# Jednoruki_bandit.net
KiCad netlist of a schematic drawn in Altium Designer
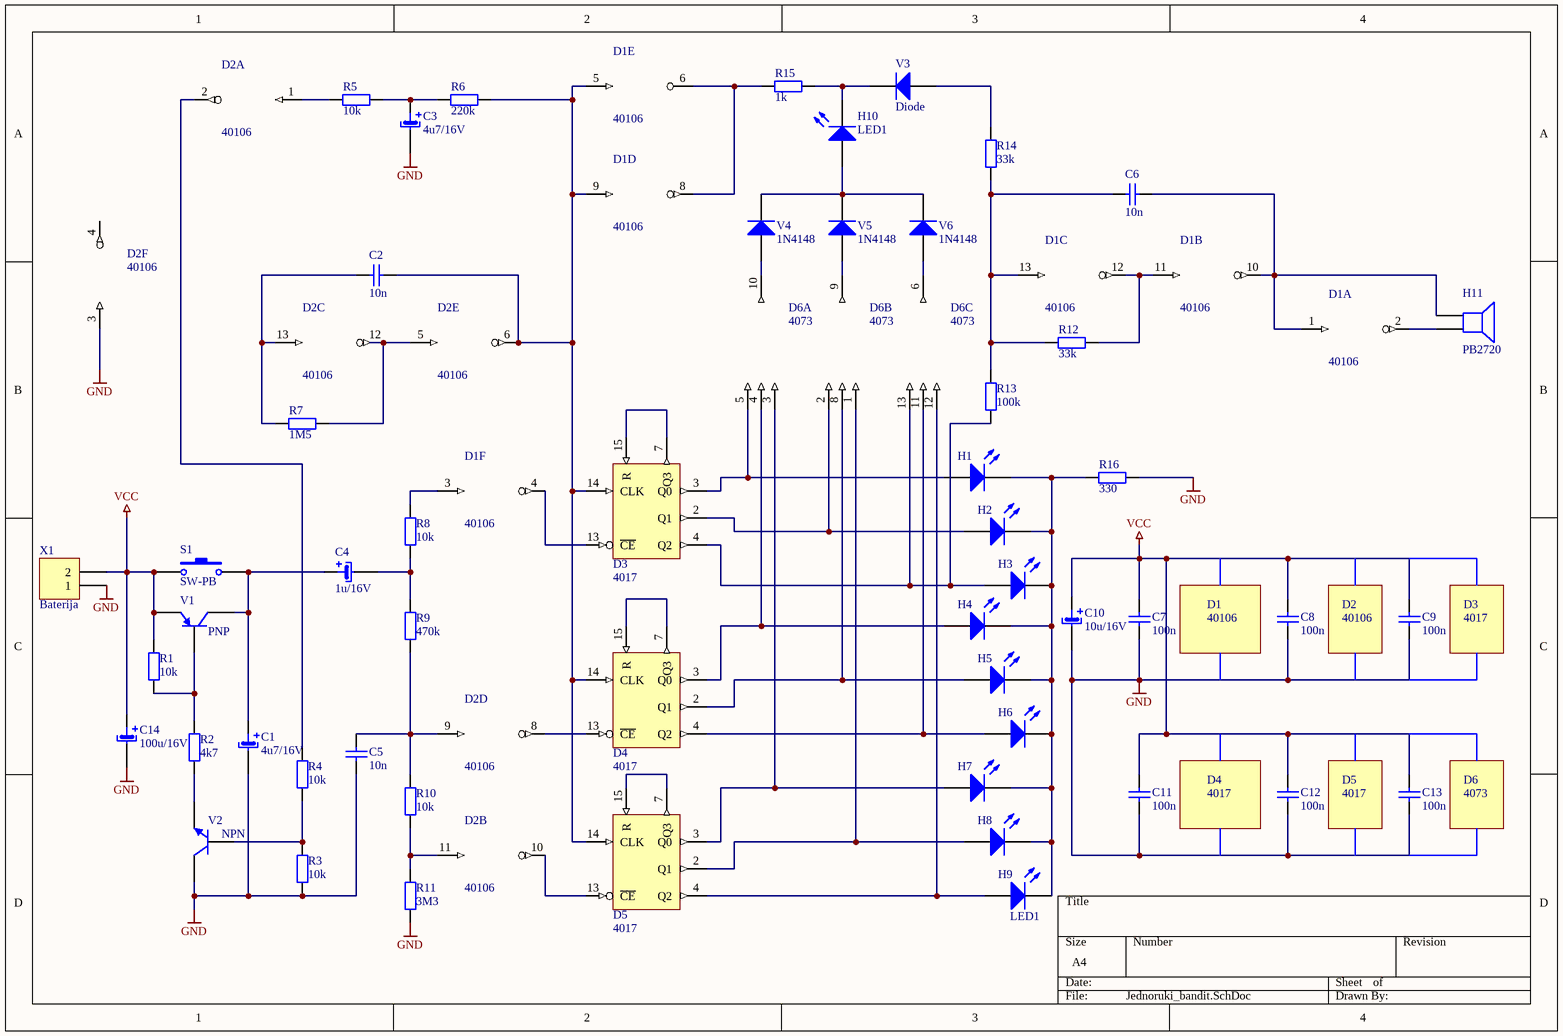
[diagram p0: Jednoruki_bandit.SchDoc]

(export (version "E")
  (design (tool "Eeschema 10.0.6"))
  (components
    (comp (ref "C1")
      (value "4u7/16V")
      (footprint "CAPPR2-5x6.8")
      (libsource (lib "moje") (part "Elektrolitski_kondenzator"))
    )
    (comp (ref "C2")
      (value "10n")
      (footprint "RAD-0.1")
      (description "Capacitor")
      (libsource (lib "Miscellaneous Devices") (part "Cap"))
    )
    (comp (ref "C3")
      (value "4u7/16V")
      (footprint "CAPPR2-5x6.8")
      (libsource (lib "moje") (part "Elektrolitski_kondenzator"))
    )
    (comp (ref "C4")
      (value "1u/16V")
      (footprint "CAPPR2-5x6.8")
      (libsource (lib "moje") (part "Elektrolitski_kondenzator"))
    )
    (comp (ref "C5")
      (value "10n")
      (footprint "RAD-0.1")
      (description "Capacitor")
      (libsource (lib "Miscellaneous Devices") (part "Cap"))
    )
    (comp (ref "C6")
      (value "10n")
      (footprint "RAD-0.1")
      (description "Capacitor")
      (libsource (lib "Miscellaneous Devices") (part "Cap"))
    )
    (comp (ref "C7")
      (value "100n")
      (footprint "RAD-0.1")
      (description "Capacitor")
      (libsource (lib "Miscellaneous Devices") (part "Cap"))
    )
    (comp (ref "C8")
      (value "100n")
      (footprint "RAD-0.1")
      (description "Capacitor")
      (libsource (lib "Miscellaneous Devices") (part "Cap"))
    )
    (comp (ref "C9")
      (value "100n")
      (footprint "RAD-0.1")
      (description "Capacitor")
      (libsource (lib "Miscellaneous Devices") (part "Cap"))
    )
    (comp (ref "C10")
      (value "10u/16V")
      (footprint "CAPPR2-5x6.8")
      (libsource (lib "moje") (part "Elektrolitski_kondenzator"))
    )
    (comp (ref "C11")
      (value "100n")
      (footprint "RAD-0.1")
      (description "Capacitor")
      (libsource (lib "Miscellaneous Devices") (part "Cap"))
    )
    (comp (ref "C12")
      (value "100n")
      (footprint "RAD-0.1")
      (description "Capacitor")
      (libsource (lib "Miscellaneous Devices") (part "Cap"))
    )
    (comp (ref "C13")
      (value "100n")
      (footprint "RAD-0.1")
      (description "Capacitor")
      (libsource (lib "Miscellaneous Devices") (part "Cap"))
    )
    (comp (ref "C14")
      (value "100u/16V")
      (footprint "CAPPR2-5x6.8")
      (libsource (lib "moje") (part "Elektrolitski_kondenzator"))
    )
    (comp (ref "D1") (value "40106") (footprint "DIP-14") (libsource (lib "moje") (part "40106")))
    (comp (ref "D2") (value "40106") (footprint "DIP-14") (libsource (lib "moje") (part "40106")))
    (comp (ref "D3") (value "4017") (footprint "DIP-16") (libsource (lib "moje") (part "4017")))
    (comp (ref "D4") (value "4017") (footprint "DIP-16") (libsource (lib "moje") (part "4017")))
    (comp (ref "D5") (value "4017") (footprint "DIP-16") (libsource (lib "moje") (part "4017")))
    (comp (ref "D6") (value "4073") (footprint "DIP-14") (libsource (lib "moje") (part "4073")))
    (comp (ref "H1")
      (value "LED1")
      (footprint "LED-1")
      (description "Typical RED GaAs LED")
      (libsource (lib "Miscellaneous Devices") (part "LED1"))
    )
    (comp (ref "H2")
      (value "LED1")
      (footprint "LED-1")
      (description "Typical RED GaAs LED")
      (libsource (lib "Miscellaneous Devices") (part "LED1"))
    )
    (comp (ref "H3")
      (value "LED1")
      (footprint "LED-1")
      (description "Typical RED GaAs LED")
      (libsource (lib "Miscellaneous Devices") (part "LED1"))
    )
    (comp (ref "H4")
      (value "LED1")
      (footprint "LED-1")
      (description "Typical RED GaAs LED")
      (libsource (lib "Miscellaneous Devices") (part "LED1"))
    )
    (comp (ref "H5")
      (value "LED1")
      (footprint "LED-1")
      (description "Typical RED GaAs LED")
      (libsource (lib "Miscellaneous Devices") (part "LED1"))
    )
    (comp (ref "H6")
      (value "LED1")
      (footprint "LED-1")
      (description "Typical RED GaAs LED")
      (libsource (lib "Miscellaneous Devices") (part "LED1"))
    )
    (comp (ref "H7")
      (value "LED1")
      (footprint "LED-1")
      (description "Typical RED GaAs LED")
      (libsource (lib "Miscellaneous Devices") (part "LED1"))
    )
    (comp (ref "H8")
      (value "LED1")
      (footprint "LED-1")
      (description "Typical RED GaAs LED")
      (libsource (lib "Miscellaneous Devices") (part "LED1"))
    )
    (comp (ref "H9")
      (value "LED1")
      (footprint "LED-1")
      (description "Typical RED GaAs LED")
      (libsource (lib "Miscellaneous Devices") (part "LED1"))
    )
    (comp (ref "H10")
      (value "LED1")
      (footprint "LED-1")
      (description "Typical RED GaAs LED")
      (libsource (lib "Miscellaneous Devices") (part "LED1"))
    )
    (comp (ref "H11")
      (value "PB2720")
      (footprint "PIN2")
      (description "Loudspeaker")
      (libsource (lib "Miscellaneous Devices") (part "Speaker"))
    )
    (comp (ref "R1")
      (value "10k")
      (footprint "AXIAL-0.4")
      (description "Resistor")
      (libsource (lib "") (part "Res2_1"))
    )
    (comp (ref "R2")
      (value "4k7")
      (footprint "AXIAL-0.4")
      (description "Resistor")
      (libsource (lib "") (part "Res2_1"))
    )
    (comp (ref "R3")
      (value "10k")
      (footprint "AXIAL-0.4")
      (description "Resistor")
      (libsource (lib "") (part "Res2_1"))
    )
    (comp (ref "R4")
      (value "10k")
      (footprint "AXIAL-0.4")
      (description "Resistor")
      (libsource (lib "") (part "Res2_1"))
    )
    (comp (ref "R5")
      (value "10k")
      (footprint "AXIAL-0.4")
      (description "Resistor")
      (libsource (lib "Miscellaneous Devices") (part "Res2"))
    )
    (comp (ref "R6")
      (value "220k")
      (footprint "AXIAL-0.4")
      (description "Resistor")
      (libsource (lib "Miscellaneous Devices") (part "Res2"))
    )
    (comp (ref "R7")
      (value "1M5")
      (footprint "AXIAL-0.4")
      (description "Resistor")
      (libsource (lib "Miscellaneous Devices") (part "Res2"))
    )
    (comp (ref "R8")
      (value "10k")
      (footprint "AXIAL-0.4")
      (description "Resistor")
      (libsource (lib "") (part "Res2_1"))
    )
    (comp (ref "R9")
      (value "470k")
      (footprint "AXIAL-0.4")
      (description "Resistor")
      (libsource (lib "") (part "Res2_1"))
    )
    (comp (ref "R10")
      (value "10k")
      (footprint "AXIAL-0.4")
      (description "Resistor")
      (libsource (lib "") (part "Res2_1"))
    )
    (comp (ref "R11")
      (value "3M3")
      (footprint "AXIAL-0.4")
      (description "Resistor")
      (libsource (lib "") (part "Res2_1"))
    )
    (comp (ref "R12")
      (value "33k")
      (footprint "AXIAL-0.4")
      (description "Resistor")
      (libsource (lib "") (part "Res2_2"))
    )
    (comp (ref "R13")
      (value "100k")
      (footprint "AXIAL-0.4")
      (description "Resistor")
      (libsource (lib "") (part "Res2_1"))
    )
    (comp (ref "R14")
      (value "33k")
      (footprint "AXIAL-0.4")
      (description "Resistor")
      (libsource (lib "") (part "Res2_1"))
    )
    (comp (ref "R15")
      (value "1k")
      (footprint "AXIAL-0.4")
      (description "Resistor")
      (libsource (lib "Miscellaneous Devices") (part "Res2"))
    )
    (comp (ref "R16")
      (value "330")
      (footprint "AXIAL-0.4")
      (description "Resistor")
      (libsource (lib "Miscellaneous Devices") (part "Res2"))
    )
    (comp (ref "S1")
      (value "SW-PB")
      (footprint "SPST-2")
      (description "Switch")
      (libsource (lib "Miscellaneous Devices") (part "SW-PB"))
    )
    (comp (ref "V1")
      (value "PNP")
      (footprint "TO-92A")
      (description "PNP Bipolar Transistor")
      (libsource (lib "Miscellaneous Devices") (part "PNP"))
    )
    (comp (ref "V2")
      (value "NPN")
      (footprint "TO-92A")
      (description "NPN Bipolar Transistor")
      (libsource (lib "Miscellaneous Devices") (part "NPN"))
    )
    (comp (ref "V3")
      (value "Diode")
      (footprint "DO-35")
      (description "Default Diode")
      (libsource (lib "Miscellaneous Devices") (part "Diode"))
    )
    (comp (ref "V4")
      (value "1N4148")
      (footprint "DIO7.1-3.9x1.9")
      (description "High Conductance Fast Diode")
      (libsource (lib "Miscellaneous Devices") (part "Diode 1N4148"))
    )
    (comp (ref "V5")
      (value "1N4148")
      (footprint "DIO7.1-3.9x1.9")
      (description "High Conductance Fast Diode")
      (libsource (lib "Miscellaneous Devices") (part "Diode 1N4148"))
    )
    (comp (ref "V6")
      (value "1N4148")
      (footprint "DIO7.1-3.9x1.9")
      (description "High Conductance Fast Diode")
      (libsource (lib "Miscellaneous Devices") (part "Diode 1N4148"))
    )
    (comp (ref "X1")
      (value "Baterija")
      (footprint "HDR1X2")
      (description "Header, 2-Pin")
      (libsource (lib "Miscellaneous Connectors") (part "Header 2"))
    )
  )
  (nets
    (net (code "1") (name "GND") (class "Default")
      (node (ref "C1") (pin "2") (pinfunction "2_2") (pintype "passive"))
      (node (ref "C10") (pin "2") (pinfunction "2_2") (pintype "passive"))
      (node (ref "C11") (pin "1") (pinfunction "1_1") (pintype "passive"))
      (node (ref "C12") (pin "1") (pinfunction "1_1") (pintype "passive"))
      (node (ref "C13") (pin "1") (pinfunction "1_1") (pintype "passive"))
      (node (ref "C14") (pin "2") (pinfunction "2_2") (pintype "passive"))
      (node (ref "C3") (pin "2") (pinfunction "2_2") (pintype "passive"))
      (node (ref "C5") (pin "1") (pinfunction "1_1") (pintype "passive"))
      (node (ref "C7") (pin "1") (pinfunction "1_1") (pintype "passive"))
      (node (ref "C8") (pin "1") (pinfunction "1_1") (pintype "passive"))
      (node (ref "C9") (pin "1") (pinfunction "1_1") (pintype "passive"))
      (node (ref "D1") (pin "7") (pinfunction "GND_7") (pintype "power_in"))
      (node (ref "D2") (pin "3") (pintype "input"))
      (node (ref "D2") (pin "7") (pinfunction "GND_7") (pintype "power_in"))
      (node (ref "D3") (pin "8") (pinfunction "GND_8") (pintype "power_in"))
      (node (ref "D4") (pin "8") (pinfunction "GND_8") (pintype "power_in"))
      (node (ref "D5") (pin "8") (pinfunction "GND_8") (pintype "power_in"))
      (node (ref "D6") (pin "7") (pinfunction "GND_7") (pintype "power_in"))
      (node (ref "R11") (pin "1") (pinfunction "1_1") (pintype "passive"))
      (node (ref "R16") (pin "2") (pinfunction "2_2") (pintype "passive"))
      (node (ref "R3") (pin "1") (pinfunction "1_1") (pintype "passive"))
      (node (ref "V2") (pin "1") (pinfunction "C_1") (pintype "passive"))
      (node (ref "X1") (pin "1") (pinfunction "1_1") (pintype "passive"))
    )
    (net (code "2") (name "Net-(C2-Pad1)") (class "Default")
      (node (ref "C2") (pin "1") (pinfunction "1_1") (pintype "passive"))
      (node (ref "D2") (pin "13") (pintype "input"))
      (node (ref "R7") (pin "1") (pinfunction "1_1") (pintype "passive"))
    )
    (net (code "3") (name "Net-(C3-Pad1)") (class "Default")
      (node (ref "C3") (pin "1") (pinfunction "1_1") (pintype "passive"))
      (node (ref "R5") (pin "2") (pinfunction "2_2") (pintype "passive"))
      (node (ref "R6") (pin "1") (pinfunction "1_1") (pintype "passive"))
    )
    (net (code "4") (name "Net-(C4-Pad2)") (class "Default")
      (node (ref "C4") (pin "2") (pinfunction "2_2") (pintype "passive"))
      (node (ref "R8") (pin "1") (pinfunction "1_1") (pintype "passive"))
      (node (ref "R9") (pin "2") (pinfunction "2_2") (pintype "passive"))
    )
    (net (code "5") (name "Net-(C5-Pad2)") (class "Default")
      (node (ref "C5") (pin "2") (pinfunction "2_2") (pintype "passive"))
      (node (ref "D2") (pin "9") (pintype "input"))
      (node (ref "R10") (pin "2") (pinfunction "2_2") (pintype "passive"))
      (node (ref "R9") (pin "1") (pinfunction "1_1") (pintype "passive"))
    )
    (net (code "6") (name "Net-(C6-Pad1)") (class "Default")
      (node (ref "C6") (pin "1") (pinfunction "1_1") (pintype "passive"))
      (node (ref "D1") (pin "13") (pintype "input"))
      (node (ref "R12") (pin "2") (pinfunction "2_2") (pintype "passive"))
      (node (ref "R13") (pin "2") (pinfunction "2_2") (pintype "passive"))
      (node (ref "R14") (pin "1") (pinfunction "1_1") (pintype "passive"))
    )
    (net (code "7") (name "Net-(C6-Pad2)") (class "Default")
      (node (ref "C6") (pin "2") (pinfunction "2_2") (pintype "passive"))
      (node (ref "D1") (pin "1") (pintype "input"))
      (node (ref "D1") (pin "10") (pintype "output"))
      (node (ref "H11") (pin "1") (pinfunction "1_1") (pintype "passive"))
    )
    (net (code "8") (name "Net-(D1-Pad2)") (class "Default")
      (node (ref "D1") (pin "2") (pintype "output"))
      (node (ref "H11") (pin "2") (pinfunction "2_2") (pintype "passive"))
    )
    (net (code "9") (name "Net-(D1-Pad3)") (class "Default")
      (node (ref "D1") (pin "3") (pintype "input"))
      (node (ref "R8") (pin "2") (pinfunction "2_2") (pintype "passive"))
    )
    (net (code "10") (name "Net-(D1-Pad6)") (class "Default")
      (node (ref "D1") (pin "6") (pintype "output"))
      (node (ref "D1") (pin "8") (pintype "output"))
      (node (ref "R15") (pin "1") (pinfunction "1_1") (pintype "passive"))
    )
    (net (code "11") (name "Net-(D1-Pad11)") (class "Default")
      (node (ref "D1") (pin "11") (pintype "input"))
      (node (ref "D1") (pin "12") (pintype "output"))
      (node (ref "R12") (pin "1") (pinfunction "1_1") (pintype "passive"))
    )
    (net (code "12") (name "Net-(D2-Pad1)") (class "Default")
      (node (ref "D2") (pin "1") (pintype "input"))
      (node (ref "R5") (pin "1") (pinfunction "1_1") (pintype "passive"))
    )
    (net (code "13") (name "Net-(D2-Pad2)") (class "Default")
      (node (ref "D2") (pin "2") (pintype "output"))
      (node (ref "R4") (pin "2") (pinfunction "2_2") (pintype "passive"))
    )
    (net (code "14") (name "Net-(D2-Pad11)") (class "Default")
      (node (ref "D2") (pin "11") (pintype "input"))
      (node (ref "R10") (pin "1") (pinfunction "1_1") (pintype "passive"))
      (node (ref "R11") (pin "2") (pinfunction "2_2") (pintype "passive"))
    )
    (net (code "15") (name "Net-(D2-Pad12)") (class "Default")
      (node (ref "D2") (pin "12") (pintype "output"))
      (node (ref "D2") (pin "5") (pintype "input"))
      (node (ref "R7") (pin "2") (pinfunction "2_2") (pintype "passive"))
    )
    (net (code "16") (name "Net-(D3-CLK)") (class "Default")
      (node (ref "C2") (pin "2") (pinfunction "2_2") (pintype "passive"))
      (node (ref "D1") (pin "5") (pintype "input"))
      (node (ref "D1") (pin "9") (pintype "input"))
      (node (ref "D2") (pin "6") (pintype "output"))
      (node (ref "D3") (pin "14") (pinfunction "CLK_14") (pintype "input"))
      (node (ref "D4") (pin "14") (pinfunction "CLK_14") (pintype "input"))
      (node (ref "D5") (pin "14") (pinfunction "CLK_14") (pintype "input"))
      (node (ref "R6") (pin "2") (pinfunction "2_2") (pintype "passive"))
    )
    (net (code "17") (name "Net-(D3-Q0)") (class "Default")
      (node (ref "D3") (pin "3") (pinfunction "Q0_3") (pintype "output"))
      (node (ref "D6") (pin "5") (pinfunction "5_5") (pintype "input"))
      (node (ref "H1") (pin "1") (pinfunction "A_1") (pintype "passive"))
    )
    (net (code "18") (name "Net-(D3-Q1)") (class "Default")
      (node (ref "D3") (pin "2") (pinfunction "Q1_2") (pintype "output"))
      (node (ref "D6") (pin "2") (pinfunction "2_2") (pintype "input"))
      (node (ref "H2") (pin "1") (pinfunction "A_1") (pintype "passive"))
    )
    (net (code "19") (name "Net-(D3-Q2)") (class "Default")
      (node (ref "D3") (pin "4") (pinfunction "Q2_4") (pintype "output"))
      (node (ref "D6") (pin "13") (pinfunction "13_13") (pintype "input"))
      (node (ref "H3") (pin "1") (pinfunction "A_1") (pintype "passive"))
      (node (ref "R13") (pin "1") (pinfunction "1_1") (pintype "passive"))
    )
    (net (code "20") (name "Net-(D3-Q3)") (class "Default")
      (node (ref "D3") (pin "15") (pinfunction "R_15") (pintype "input"))
      (node (ref "D3") (pin "7") (pinfunction "Q3_7") (pintype "output"))
    )
    (net (code "21") (name "Net-(D3-~{CE})") (class "Default")
      (node (ref "D1") (pin "4") (pintype "output"))
      (node (ref "D3") (pin "13") (pinfunction "~{CE}_13") (pintype "input"))
    )
    (net (code "22") (name "Net-(D4-Q0)") (class "Default")
      (node (ref "D4") (pin "3") (pinfunction "Q0_3") (pintype "output"))
      (node (ref "D6") (pin "4") (pinfunction "4_4") (pintype "input"))
      (node (ref "H4") (pin "1") (pinfunction "A_1") (pintype "passive"))
    )
    (net (code "23") (name "Net-(D4-Q1)") (class "Default")
      (node (ref "D4") (pin "2") (pinfunction "Q1_2") (pintype "output"))
      (node (ref "D6") (pin "8") (pinfunction "8_8") (pintype "input"))
      (node (ref "H5") (pin "1") (pinfunction "A_1") (pintype "passive"))
    )
    (net (code "24") (name "Net-(D4-Q2)") (class "Default")
      (node (ref "D4") (pin "4") (pinfunction "Q2_4") (pintype "output"))
      (node (ref "D6") (pin "11") (pinfunction "11_11") (pintype "input"))
      (node (ref "H6") (pin "1") (pinfunction "A_1") (pintype "passive"))
    )
    (net (code "25") (name "Net-(D4-Q3)") (class "Default")
      (node (ref "D4") (pin "15") (pinfunction "R_15") (pintype "input"))
      (node (ref "D4") (pin "7") (pinfunction "Q3_7") (pintype "output"))
    )
    (net (code "26") (name "Net-(D4-~{CE})") (class "Default")
      (node (ref "D2") (pin "8") (pintype "output"))
      (node (ref "D4") (pin "13") (pinfunction "~{CE}_13") (pintype "input"))
    )
    (net (code "27") (name "Net-(D5-Q0)") (class "Default")
      (node (ref "D5") (pin "3") (pinfunction "Q0_3") (pintype "output"))
      (node (ref "D6") (pin "3") (pinfunction "3_3") (pintype "input"))
      (node (ref "H7") (pin "1") (pinfunction "A_1") (pintype "passive"))
    )
    (net (code "28") (name "Net-(D5-Q1)") (class "Default")
      (node (ref "D5") (pin "2") (pinfunction "Q1_2") (pintype "output"))
      (node (ref "D6") (pin "1") (pinfunction "1_1") (pintype "input"))
      (node (ref "H8") (pin "1") (pinfunction "A_1") (pintype "passive"))
    )
    (net (code "29") (name "Net-(D5-Q2)") (class "Default")
      (node (ref "D5") (pin "4") (pinfunction "Q2_4") (pintype "output"))
      (node (ref "D6") (pin "12") (pinfunction "12_12") (pintype "input"))
      (node (ref "H9") (pin "1") (pinfunction "A_1") (pintype "passive"))
    )
    (net (code "30") (name "Net-(D5-Q3)") (class "Default")
      (node (ref "D5") (pin "15") (pinfunction "R_15") (pintype "input"))
      (node (ref "D5") (pin "7") (pinfunction "Q3_7") (pintype "output"))
    )
    (net (code "31") (name "Net-(D5-~{CE})") (class "Default")
      (node (ref "D2") (pin "10") (pintype "output"))
      (node (ref "D5") (pin "13") (pinfunction "~{CE}_13") (pintype "input"))
    )
    (net (code "32") (name "Net-(H1-K)") (class "Default")
      (node (ref "H1") (pin "2") (pinfunction "K_2") (pintype "passive"))
      (node (ref "H2") (pin "2") (pinfunction "K_2") (pintype "passive"))
      (node (ref "H3") (pin "2") (pinfunction "K_2") (pintype "passive"))
      (node (ref "H4") (pin "2") (pinfunction "K_2") (pintype "passive"))
      (node (ref "H5") (pin "2") (pinfunction "K_2") (pintype "passive"))
      (node (ref "H6") (pin "2") (pinfunction "K_2") (pintype "passive"))
      (node (ref "H7") (pin "2") (pinfunction "K_2") (pintype "passive"))
      (node (ref "H8") (pin "2") (pinfunction "K_2") (pintype "passive"))
      (node (ref "H9") (pin "2") (pinfunction "K_2") (pintype "passive"))
      (node (ref "R16") (pin "1") (pinfunction "1_1") (pintype "passive"))
    )
    (net (code "33") (name "Net-(H10-A)") (class "Default")
      (node (ref "H10") (pin "1") (pinfunction "A_1") (pintype "passive"))
      (node (ref "V4") (pin "2") (pinfunction "K_2") (pintype "passive"))
      (node (ref "V5") (pin "2") (pinfunction "K_2") (pintype "passive"))
      (node (ref "V6") (pin "2") (pinfunction "K_2") (pintype "passive"))
    )
    (net (code "34") (name "Net-(H10-K)") (class "Default")
      (node (ref "H10") (pin "2") (pinfunction "K_2") (pintype "passive"))
      (node (ref "R15") (pin "2") (pinfunction "2_2") (pintype "passive"))
      (node (ref "V3") (pin "2") (pinfunction "K_2") (pintype "passive"))
    )
    (net (code "35") (name "Net-(V1-B)") (class "Default")
      (node (ref "R1") (pin "1") (pinfunction "1_1") (pintype "passive"))
      (node (ref "R2") (pin "2") (pinfunction "2_2") (pintype "passive"))
      (node (ref "V1") (pin "2") (pinfunction "B_2") (pintype "passive"))
    )
    (net (code "36") (name "Net-(V1-C)") (class "Default")
      (node (ref "C1") (pin "1") (pinfunction "1_1") (pintype "passive"))
      (node (ref "C4") (pin "1") (pinfunction "1_1") (pintype "passive"))
      (node (ref "S1") (pin "2") (pinfunction "2_2") (pintype "passive"))
      (node (ref "V1") (pin "1") (pinfunction "C_1") (pintype "passive"))
    )
    (net (code "37") (name "Net-(V2-B)") (class "Default")
      (node (ref "R3") (pin "2") (pinfunction "2_2") (pintype "passive"))
      (node (ref "R4") (pin "1") (pinfunction "1_1") (pintype "passive"))
      (node (ref "V2") (pin "2") (pinfunction "B_2") (pintype "passive"))
    )
    (net (code "38") (name "Net-(V2-E)") (class "Default")
      (node (ref "R2") (pin "1") (pinfunction "1_1") (pintype "passive"))
      (node (ref "V2") (pin "3") (pinfunction "E_3") (pintype "passive"))
    )
    (net (code "39") (name "Net-(V3-A)") (class "Default")
      (node (ref "R14") (pin "2") (pinfunction "2_2") (pintype "passive"))
      (node (ref "V3") (pin "1") (pinfunction "A_1") (pintype "passive"))
    )
    (net (code "40") (name "Net-(V4-A)") (class "Default")
      (node (ref "D6") (pin "10") (pinfunction "10_10") (pintype "output"))
      (node (ref "V4") (pin "1") (pinfunction "A_1") (pintype "passive"))
    )
    (net (code "41") (name "Net-(V5-A)") (class "Default")
      (node (ref "D6") (pin "9") (pinfunction "9_9") (pintype "output"))
      (node (ref "V5") (pin "1") (pinfunction "A_1") (pintype "passive"))
    )
    (net (code "42") (name "Net-(V6-A)") (class "Default")
      (node (ref "D6") (pin "6") (pinfunction "6_6") (pintype "output"))
      (node (ref "V6") (pin "1") (pinfunction "A_1") (pintype "passive"))
    )
    (net (code "43") (name "VCC") (class "Default")
      (node (ref "C10") (pin "1") (pinfunction "1_1") (pintype "passive"))
      (node (ref "C11") (pin "2") (pinfunction "2_2") (pintype "passive"))
      (node (ref "C12") (pin "2") (pinfunction "2_2") (pintype "passive"))
      (node (ref "C13") (pin "2") (pinfunction "2_2") (pintype "passive"))
      (node (ref "C14") (pin "1") (pinfunction "1_1") (pintype "passive"))
      (node (ref "C7") (pin "2") (pinfunction "2_2") (pintype "passive"))
      (node (ref "C8") (pin "2") (pinfunction "2_2") (pintype "passive"))
      (node (ref "C9") (pin "2") (pinfunction "2_2") (pintype "passive"))
      (node (ref "D1") (pin "14") (pinfunction "VCC_14") (pintype "power_in"))
      (node (ref "D2") (pin "14") (pinfunction "VCC_14") (pintype "power_in"))
      (node (ref "D3") (pin "16") (pinfunction "VCC_16") (pintype "power_in"))
      (node (ref "D4") (pin "16") (pinfunction "VCC_16") (pintype "power_in"))
      (node (ref "D5") (pin "16") (pinfunction "VCC_16") (pintype "power_in"))
      (node (ref "D6") (pin "14") (pinfunction "VCC_14") (pintype "power_in"))
      (node (ref "R1") (pin "2") (pinfunction "2_2") (pintype "passive"))
      (node (ref "S1") (pin "1") (pinfunction "1_1") (pintype "passive"))
      (node (ref "V1") (pin "3") (pinfunction "E_3") (pintype "passive"))
      (node (ref "X1") (pin "2") (pinfunction "2_2") (pintype "passive"))
    )
    (net (code "44") (name "unconnected-(D2-Pad4)") (class "Default")
      (node (ref "D2") (pin "4") (pintype "output"))
    )
  )
)
